# rev-b.net
KiCad netlist of a schematic drawn in EAGLE
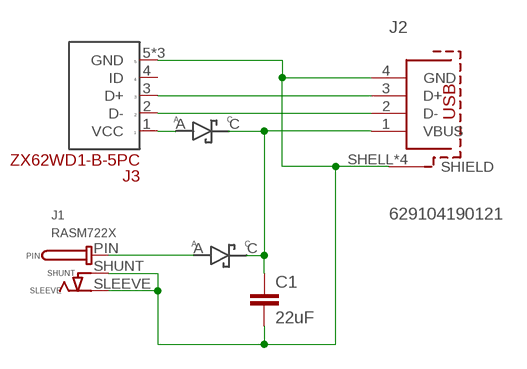
[diagram p0: schematic, sheet 1]

(export (version "E")
  (design (tool "Eeschema 10.0.6"))
  (components
    (comp (ref "C1")
      (value "22uF")
      (footprint "eagle-import:1206")
      (libsource (lib "eagle-import") (part "2.2UF-1206-50V-10%"))
    )
    (comp (ref "D1")
      (value "PMEG6030ETP")
      (footprint "eagle-import:SOD128")
      (libsource (lib "eagle-import") (part "PMEG6030ETP"))
    )
    (comp (ref "D2")
      (value "PMEG6030ETP")
      (footprint "eagle-import:SOD128")
      (libsource (lib "eagle-import") (part "PMEG6030ETP"))
    )
    (comp (ref "J1")
      (value "RASM722X")
      (footprint "eagle-import:SWITCHCRAFT_RASM722X")
      (fields (field (name "MF") "Switchcraft"))
      (libsource (lib "eagle-import") (part "RASM722X"))
    )
    (comp (ref "J2")
      (value "629104190121")
      (footprint "eagle-import:629104190121")
      (fields (field (name "MF") "Würth Elektronik"))
      (libsource (lib "eagle-import") (part "629104190121"))
    )
    (comp (ref "J3")
      (value "ZX62WD1-B-5PC")
      (footprint "eagle-import:ZX62WD1-B-5PC")
      (libsource (lib "eagle-import") (part "ZX62WD1-B-5PC"))
    )
  )
  (nets
    (net (code "1") (name "Net-(D1-PadA)") (class "Default")
      (node (ref "D1") (pin "A") (pinfunction "A_A") (pintype "bidirectional"))
      (node (ref "J1") (pin "PIN") (pinfunction "PIN_PIN") (pintype "bidirectional"))
    )
    (net (code "2") (name "Net-(J2-D+)") (class "Default")
      (node (ref "J2") (pin "3") (pinfunction "D+_3") (pintype "bidirectional"))
      (node (ref "J3") (pin "3") (pinfunction "D+_3") (pintype "bidirectional"))
    )
    (net (code "3") (name "Net-(J2-D-)") (class "Default")
      (node (ref "J2") (pin "2") (pinfunction "D-_2") (pintype "bidirectional"))
      (node (ref "J3") (pin "2") (pinfunction "D-_2") (pintype "bidirectional"))
    )
    (net (code "4") (name "Net-(J2-GND)") (class "Default")
      (node (ref "C1") (pin "2") (pinfunction "2_2") (pintype "passive"))
      (node (ref "J1") (pin "SHUNT") (pinfunction "SHUNT_SHUNT") (pintype "power_in"))
      (node (ref "J1") (pin "SLEEVE") (pinfunction "SLEEVE_SLEEVE") (pintype "power_in"))
      (node (ref "J2") (pin "4") (pinfunction "GND_4") (pintype "bidirectional"))
      (node (ref "J2") (pin "SHELL") (pinfunction "SHIELD_SHELL") (pintype "bidirectional"))
      (node (ref "J2") (pin "SHELL1") (pinfunction "SHIELD_SHELL1") (pintype "bidirectional"))
      (node (ref "J2") (pin "SHELL2") (pinfunction "SHIELD_SHELL2") (pintype "bidirectional"))
      (node (ref "J2") (pin "SHELL3") (pinfunction "SHIELD_SHELL3") (pintype "bidirectional"))
      (node (ref "J3") (pin "5") (pinfunction "GND_5") (pintype "bidirectional"))
      (node (ref "J3") (pin "P$1") (pinfunction "GND_P$1") (pintype "bidirectional"))
      (node (ref "J3") (pin "P$2") (pinfunction "GND_P$2") (pintype "bidirectional"))
    )
    (net (code "5") (name "Net-(J2-VBUS)") (class "Default")
      (node (ref "C1") (pin "1") (pinfunction "1_1") (pintype "passive"))
      (node (ref "D1") (pin "C") (pinfunction "C_C") (pintype "bidirectional"))
      (node (ref "D2") (pin "C") (pinfunction "C_C") (pintype "bidirectional"))
      (node (ref "J2") (pin "1") (pinfunction "VBUS_1") (pintype "bidirectional"))
    )
    (net (code "6") (name "Net-(J3-VCC)") (class "Default")
      (node (ref "D2") (pin "A") (pinfunction "A_A") (pintype "bidirectional"))
      (node (ref "J3") (pin "1") (pinfunction "VCC_1") (pintype "bidirectional"))
    )
    (net (code "7") (name "unconnected-(J3-ID-Pad4)") (class "Default")
      (node (ref "J3") (pin "4") (pinfunction "ID_4") (pintype "bidirectional"))
    )
  )
)
